# POWER_SUPPLY.net
KiCad netlist of a schematic drawn in Altium Designer
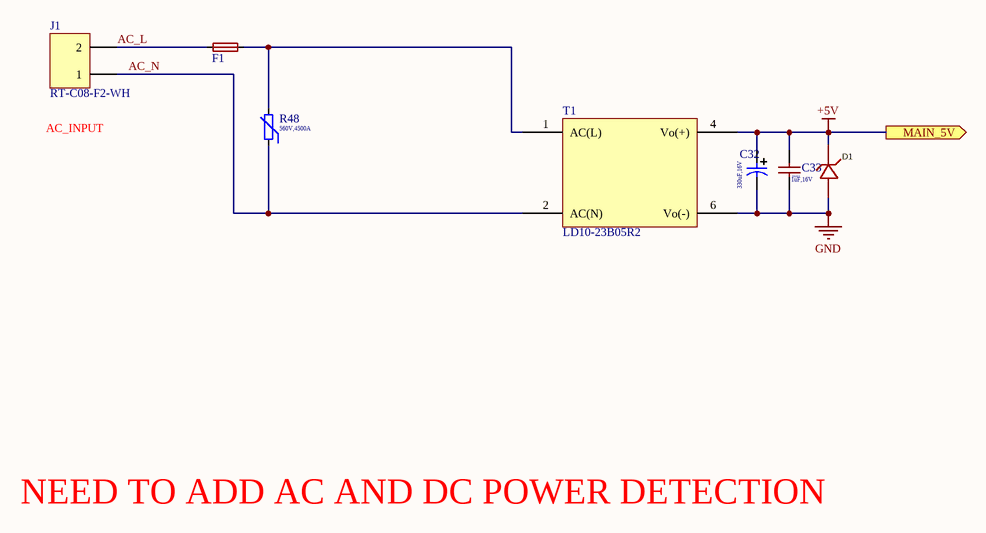
[diagram p0: POWER SUPPLY.SchDoc]

(export (version "E")
  (design (tool "Eeschema 10.0.6"))
  (components
    (comp (ref "C32")
      (value "330uF,16V")
      (footprint "D10xL10.2mm")
      (description "330uF 16V ±20% SMD,D10xL10mm Aluminum Electrolytic Capacitors - SMD ROHS")
      (fields (field (name "MANUFACTURER") "Lelon") (field (name "MPN") "VUX331M1CTR-1010"))
      (libsource (lib "RCL") (part "VUX331M1CTR-1010"))
    )
    (comp (ref "C33")
      (value "1uF,16V")
      (footprint "C0603")
      (description "16V 1uF X7R ±10% 0603 Multilayer Ceramic Capacitors MLCC - SMD/SMT ROHS")
      (fields
        (field (name "MANUFACTURER") "Samsung Electro-Mechanics")
        (field (name "MPN") "CL10B105KO8NNNC")
        (field (name "PACKAGE") "0603")
      )
      (libsource (lib "RCL") (part "CL10B105KO8NNNC"))
    )
    (comp (ref "D1")
      (value "SMBJ7.0A")
      (footprint "SMB(DO-214AA)")
      (description "50A 12V 7.78V Unidirectional 7V SMB(DO-214AA) ESD and Surge Protection (TVS/ESD) ROHS")
      (fields (field (name "MANUFACTURER") "FTR"))
      (libsource (lib "RCL") (part "SMBJ7.0A"))
    )
    (comp (ref "F1")
      (value "2009T2A250V")
      (footprint "F1")
      (description "Plugin Fuses ROHS")
      (fields (field (name "MANUFACTURER") "Hongda"))
      (libsource (lib "RCL") (part "2009T2A250V"))
    )
    (comp (ref "J1")
      (value "RT-C08-F2-WH")
      (footprint "AC POWER PORT")
      (description "Plugin AC Power Connectors ROHS")
      (fields (field (name "MANUFACTURER") "Legion"))
      (libsource (lib "connector_button") (part "RT-C08-F2-WH"))
    )
    (comp (ref "R48")
      (value "560V,4500A")
      (footprint "DIP-2(VR)")
      (description "560 V 4.5 kA Varistor 1 Circuit Through Hole Disc 14mm")
      (fields
        (field (name "MANUFACTURER") "Shenzhen Ruilongyuan Electronics Co.Ltd")
        (field (name "MPN") "14D561K")
      )
      (libsource (lib "RCL") (part "14D561K"))
    )
    (comp (ref "T1")
      (value "LD10-23B05R2")
      (footprint "DIP-4(LD10-23B05R2)")
      (description "Power supply module,Power Supplies ROHS")
      (fields (field (name "MANUFACTURER") "LZTEC"))
      (libsource (lib "IC") (part "LD10-23B05R2"))
    )
  )
  (nets
    (net (code "1") (name "+5V") (class "Default")
      (node (ref "C32") (pin "1") (pinfunction "1_1") (pintype "passive"))
      (node (ref "C33") (pin "2") (pinfunction "2_2") (pintype "passive"))
      (node (ref "D1") (pin "1") (pinfunction "C_1") (pintype "passive"))
      (node (ref "T1") (pin "4") (pinfunction "Vo(+)_4") (pintype "passive"))
    )
    (net (code "2") (name "/AC_L") (class "Default")
      (node (ref "F1") (pin "1") (pinfunction "1_1") (pintype "passive"))
      (node (ref "J1") (pin "2") (pinfunction "2_2") (pintype "passive"))
    )
    (net (code "3") (name "/AC_N") (class "Default")
      (node (ref "J1") (pin "1") (pinfunction "1_1") (pintype "passive"))
      (node (ref "R48") (pin "1") (pinfunction "1_1") (pintype "passive"))
      (node (ref "T1") (pin "2") (pinfunction "AC(N)_2") (pintype "passive"))
    )
    (net (code "4") (name "GND") (class "Default")
      (node (ref "C32") (pin "2") (pinfunction "2_2") (pintype "passive"))
      (node (ref "C33") (pin "1") (pinfunction "1_1") (pintype "passive"))
      (node (ref "D1") (pin "2") (pinfunction "A_2") (pintype "passive"))
      (node (ref "T1") (pin "6") (pinfunction "Vo(-)_6") (pintype "passive"))
    )
    (net (code "5") (name "Net-(T1-AC(L))") (class "Default")
      (node (ref "F1") (pin "2") (pinfunction "2_2") (pintype "passive"))
      (node (ref "R48") (pin "2") (pinfunction "2_2") (pintype "passive"))
      (node (ref "T1") (pin "1") (pinfunction "AC(L)_1") (pintype "passive"))
    )
  )
)
